# Allimentations.net
KiCad netlist of a schematic drawn in Altium Designer
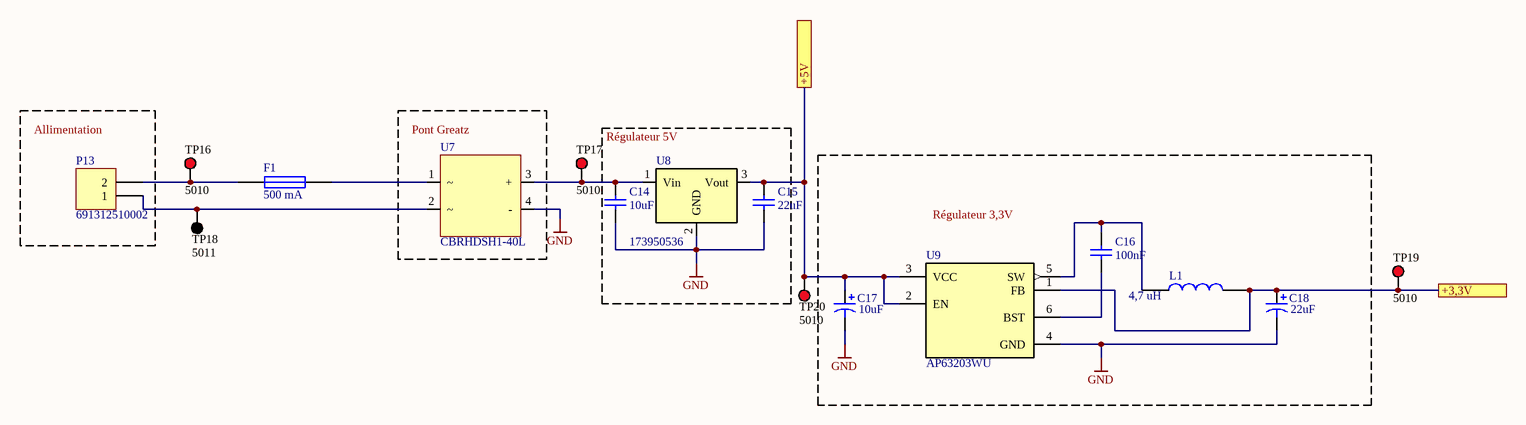
[diagram p0: Allimentations.SchDoc]

(export (version "E")
  (design (tool "Eeschema 10.0.6"))
  (components
    (comp (ref "C14")
      (value "10uF")
      (footprint "C0805")
      (description "Capacitor")
      (fields (field (name "Comment") "Cap") (field (name "PUBLISHER") "Altium Limited"))
      (libsource (lib "Miscellaneous Devices") (part "Cap"))
    )
    (comp (ref "C15")
      (value "22uF")
      (footprint "C0805")
      (description "Capacitor")
      (fields (field (name "Comment") "Cap") (field (name "PUBLISHER") "Altium Limited"))
      (libsource (lib "Miscellaneous Devices") (part "Cap"))
    )
    (comp (ref "C16")
      (value "100nF")
      (footprint "C0805")
      (description "Capacitor")
      (fields (field (name "Comment") "Cap") (field (name "PUBLISHER") "Altium Limited"))
      (libsource (lib "Miscellaneous Devices") (part "Cap"))
    )
    (comp (ref "C17")
      (value "10uF")
      (footprint "CAP_EEEFK1E331GP")
      (description "Polarized Capacitor (Radial)")
      (fields (field (name "Comment") "Cap Pol1") (field (name "PUBLISHER") "Altium Limited"))
      (libsource (lib "Miscellaneous Devices") (part "Cap Pol1"))
    )
    (comp (ref "C18")
      (value "22uF")
      (footprint "CAP_EEEFK1E331GP")
      (description "Polarized Capacitor (Radial)")
      (fields (field (name "Comment") "Cap Pol1") (field (name "PUBLISHER") "Altium Limited"))
      (libsource (lib "Miscellaneous Devices") (part "Cap Pol1"))
    )
    (comp (ref "F1")
      (value "500 mA")
      (footprint "PIN-W2/E2.8")
      (description "Fuse")
      (fields (field (name "PUBLISHER") "Altium Limited"))
      (libsource (lib "Miscellaneous Devices") (part "Fuse 1"))
    )
    (comp (ref "L1")
      (value "4,7 uH")
      (footprint "CDRH125101MC")
      (description "Fixed Inductors 22uH 2.80A 0.028ohms")
      (fields (field (name "MANUFACTURER_PART_NUMBER") "CDRH125NP-220MC"))
      (libsource (lib "TP2_Convertisseur_Courant") (part "CDRH125NP-220MC"))
    )
    (comp (ref "P13")
      (value "691312510002")
      (footprint "691312710002")
      (description "Header, 2-Pin")
      (fields (field (name "PUBLISHER") "Altium Limited"))
      (libsource (lib "Miscellaneous Connectors") (part "MHDR1X2"))
    )
    (comp (ref "TP16")
      (value "5010")
      (footprint "KSTN-5010_V")
      (description "Test Point, Red, Through Hole, RoHS, Bulk")
      (fields (field (name "MANUFACTURER") "Keystone"))
      (libsource (lib "Altium Content Vault") (part "TESTPOINT_RED"))
    )
    (comp (ref "TP17")
      (value "5010")
      (footprint "KSTN-5010_V")
      (description "Test Point, Red, Through Hole, RoHS, Bulk")
      (fields (field (name "MANUFACTURER") "Keystone"))
      (libsource (lib "Altium Content Vault") (part "TESTPOINT_RED"))
    )
    (comp (ref "TP18")
      (value "5011")
      (footprint "KSTN-5011_V")
      (description "Test Point, Black, Through Hole, RoHS, Bulk")
      (fields (field (name "MANUFACTURER") "Keystone"))
      (libsource (lib "Altium Content Vault") (part "TESTPOINT_BLACK"))
    )
    (comp (ref "TP19")
      (value "5010")
      (footprint "KSTN-5010_V")
      (description "Test Point, Red, Through Hole, RoHS, Bulk")
      (fields (field (name "MANUFACTURER") "Keystone"))
      (libsource (lib "Altium Content Vault") (part "TESTPOINT_RED"))
    )
    (comp (ref "TP20")
      (value "5010")
      (footprint "KSTN-5010_V")
      (description "Test Point, Red, Through Hole, RoHS, Bulk")
      (fields (field (name "MANUFACTURER") "Keystone"))
      (libsource (lib "Altium Content Vault") (part "TESTPOINT_RED"))
    )
    (comp (ref "U7")
      (value "CBRHDSH1-40L")
      (footprint "CBRHDSH1-40L")
      (libsource (lib "2227_BoiteBruitage") (part "CBRHDSH1-40L"))
    )
    (comp (ref "U8")
      (value "173950536")
      (footprint "173950536")
      (libsource (lib "2227_BoiteBruitage") (part "173950536"))
    )
    (comp (ref "U9")
      (value "AP63203WU")
      (footprint "AP63203WU")
      (libsource (lib "2227_BoiteBruitage") (part "AP63203WU"))
    )
  )
  (nets
    (net (code "1") (name "/+3,3V") (class "Default")
      (node (ref "C18") (pin "1") (pinfunction "1_1") (pintype "passive"))
      (node (ref "L1") (pin "2") (pinfunction "2_2") (pintype "passive"))
      (node (ref "TP19") (pin "1") (pinfunction "1_1") (pintype "passive"))
      (node (ref "U9") (pin "1") (pinfunction "FB_1") (pintype "passive"))
    )
    (net (code "2") (name "/+5V") (class "Default")
      (node (ref "C15") (pin "2") (pinfunction "2_2") (pintype "passive"))
      (node (ref "C17") (pin "1") (pinfunction "1_1") (pintype "passive"))
      (node (ref "TP20") (pin "1") (pinfunction "1_1") (pintype "passive"))
      (node (ref "U8") (pin "3") (pinfunction "Vout_3") (pintype "passive"))
      (node (ref "U9") (pin "2") (pinfunction "EN_2") (pintype "passive"))
      (node (ref "U9") (pin "3") (pinfunction "VCC_3") (pintype "passive"))
    )
    (net (code "3") (name "GND") (class "Default")
      (node (ref "C14") (pin "1") (pinfunction "1_1") (pintype "passive"))
      (node (ref "C15") (pin "1") (pinfunction "1_1") (pintype "passive"))
      (node (ref "C17") (pin "2") (pinfunction "2_2") (pintype "passive"))
      (node (ref "C18") (pin "2") (pinfunction "2_2") (pintype "passive"))
      (node (ref "U7") (pin "4") (pinfunction "-_4") (pintype "passive"))
      (node (ref "U8") (pin "2") (pinfunction "GND_2") (pintype "passive"))
      (node (ref "U9") (pin "4") (pinfunction "GND_4") (pintype "power_in"))
    )
    (net (code "4") (name "Net-(F1-Pad1)") (class "Default")
      (node (ref "F1") (pin "1") (pinfunction "1_1") (pintype "passive"))
      (node (ref "P13") (pin "2") (pinfunction "2_2") (pintype "passive"))
      (node (ref "TP16") (pin "1") (pinfunction "1_1") (pintype "passive"))
    )
    (net (code "5") (name "Net-(F1-Pad2)") (class "Default")
      (node (ref "F1") (pin "2") (pinfunction "2_2") (pintype "passive"))
      (node (ref "U7") (pin "1") (pinfunction "~_1") (pintype "passive"))
    )
    (net (code "6") (name "Net-(P13-Pad1)") (class "Default")
      (node (ref "P13") (pin "1") (pinfunction "1_1") (pintype "passive"))
      (node (ref "TP18") (pin "1") (pinfunction "1_1") (pintype "passive"))
      (node (ref "U7") (pin "2") (pinfunction "~_2") (pintype "passive"))
    )
    (net (code "7") (name "Net-(U7-+)") (class "Default")
      (node (ref "C14") (pin "2") (pinfunction "2_2") (pintype "passive"))
      (node (ref "TP17") (pin "1") (pinfunction "1_1") (pintype "passive"))
      (node (ref "U7") (pin "3") (pinfunction "+_3") (pintype "passive"))
      (node (ref "U8") (pin "1") (pinfunction "Vin_1") (pintype "passive"))
    )
    (net (code "8") (name "Net-(U9-BST)") (class "Default")
      (node (ref "C16") (pin "1") (pinfunction "1_1") (pintype "passive"))
      (node (ref "U9") (pin "6") (pinfunction "BST_6") (pintype "power_in"))
    )
    (net (code "9") (name "Net-(U9-SW)") (class "Default")
      (node (ref "C16") (pin "2") (pinfunction "2_2") (pintype "passive"))
      (node (ref "L1") (pin "1") (pinfunction "1_1") (pintype "passive"))
      (node (ref "U9") (pin "5") (pinfunction "SW_5") (pintype "output"))
    )
  )
)
